# POWER_SECTION.net
KiCad netlist of a schematic drawn in Altium Designer
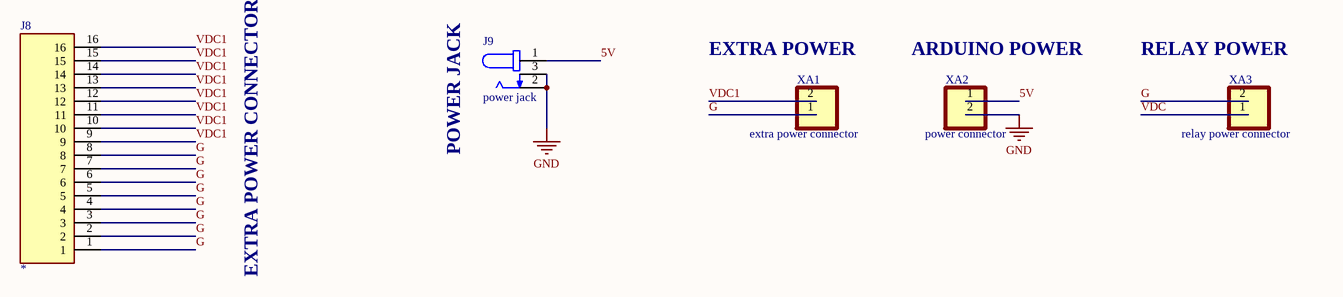
[diagram p0: POWER SECTION.SchDoc]

(export (version "E")
  (design (tool "Eeschema 10.0.6"))
  (components
    (comp (ref "J8")
      (value "1-215297-6")
      (footprint "TE_1-215297-6")
      (fields (field (name "MF") "TE Connectivity") (field (name "COMMENT_1") "*"))
      (libsource (lib "16pin female header 3D") (part "1-215297-6"))
    )
    (comp (ref "J9")
      (value "power jack")
      (footprint "CUI_PJ-202A")
      (description "2.0 x 6.5 mm, 2.5 A, Horizontal, Through Hole, Kinked Pins, Dc Power Jack Connector")
      (fields (field (name "MP") "PJ-202A") (field (name "MF") "CUI Devices"))
      (libsource (lib "DC pin with 3D") (part "PJ-202A"))
    )
    (comp (ref "XA1")
      (value "extra power connector")
      (footprint "PHOENIX_MKDS1/2-3.81")
      (description "2 Position Wire to Board Terminal Block Horizontal with Board 0.150 _3.81mm_ Through Hole")
      (fields (field (name "MF") "Phoenix Contact") (field (name "MP") "MKDS 1/ 2-3.81"))
      (libsource (lib "connector 2 pin 3D1") (part "MKDS1/2-3.81"))
    )
    (comp (ref "XA2")
      (value "power connector")
      (footprint "PHOENIX_MKDS1/2-3.81")
      (description "2 Position Wire to Board Terminal Block Horizontal with Board 0.150 _3.81mm_ Through Hole")
      (fields (field (name "MF") "Phoenix Contact") (field (name "MP") "MKDS 1/ 2-3.81"))
      (libsource (lib "") (part "MKDS1/2-3.81_1"))
    )
    (comp (ref "XA3")
      (value "relay power connector")
      (footprint "PHOENIX_MKDS1/2-3.81")
      (description "2 Position Wire to Board Terminal Block Horizontal with Board 0.150 _3.81mm_ Through Hole")
      (fields (field (name "MF") "Phoenix Contact") (field (name "MP") "MKDS 1/ 2-3.81"))
      (libsource (lib "connector 2 pin 3D1") (part "MKDS1/2-3.81"))
    )
  )
  (nets
    (net (code "1") (name "/5V") (class "Default")
      (node (ref "J9") (pin "1") (pinfunction "1_1") (pintype "passive"))
      (node (ref "XA2") (pin "1") (pinfunction "1_1") (pintype "passive"))
    )
    (net (code "2") (name "/G") (class "Default")
      (node (ref "J8") (pin "1") (pinfunction "1_1") (pintype "passive"))
      (node (ref "J8") (pin "2") (pinfunction "2_2") (pintype "passive"))
      (node (ref "J8") (pin "3") (pinfunction "3_3") (pintype "passive"))
      (node (ref "J8") (pin "4") (pinfunction "4_4") (pintype "passive"))
      (node (ref "J8") (pin "5") (pinfunction "5_5") (pintype "passive"))
      (node (ref "J8") (pin "6") (pinfunction "6_6") (pintype "passive"))
      (node (ref "J8") (pin "7") (pinfunction "7_7") (pintype "passive"))
      (node (ref "J8") (pin "8") (pinfunction "8_8") (pintype "passive"))
      (node (ref "XA1") (pin "1") (pinfunction "1_1") (pintype "passive"))
      (node (ref "XA3") (pin "2") (pinfunction "2_2") (pintype "passive"))
    )
    (net (code "3") (name "/VDC") (class "Default")
      (node (ref "XA3") (pin "1") (pinfunction "1_1") (pintype "passive"))
    )
    (net (code "4") (name "/VDC1") (class "Default")
      (node (ref "J8") (pin "10") (pinfunction "10_10") (pintype "passive"))
      (node (ref "J8") (pin "11") (pinfunction "11_11") (pintype "passive"))
      (node (ref "J8") (pin "12") (pinfunction "12_12") (pintype "passive"))
      (node (ref "J8") (pin "13") (pinfunction "13_13") (pintype "passive"))
      (node (ref "J8") (pin "14") (pinfunction "14_14") (pintype "passive"))
      (node (ref "J8") (pin "15") (pinfunction "15_15") (pintype "passive"))
      (node (ref "J8") (pin "16") (pinfunction "16_16") (pintype "passive"))
      (node (ref "J8") (pin "9") (pinfunction "9_9") (pintype "passive"))
      (node (ref "XA1") (pin "2") (pinfunction "2_2") (pintype "passive"))
    )
    (net (code "5") (name "GND") (class "Default")
      (node (ref "J9") (pin "2") (pinfunction "2_2") (pintype "passive"))
      (node (ref "J9") (pin "3") (pinfunction "3_3") (pintype "passive"))
      (node (ref "XA2") (pin "2") (pinfunction "2_2") (pintype "passive"))
    )
  )
)
